# FordACPAUX.net
KiCad netlist of a schematic drawn in EAGLE
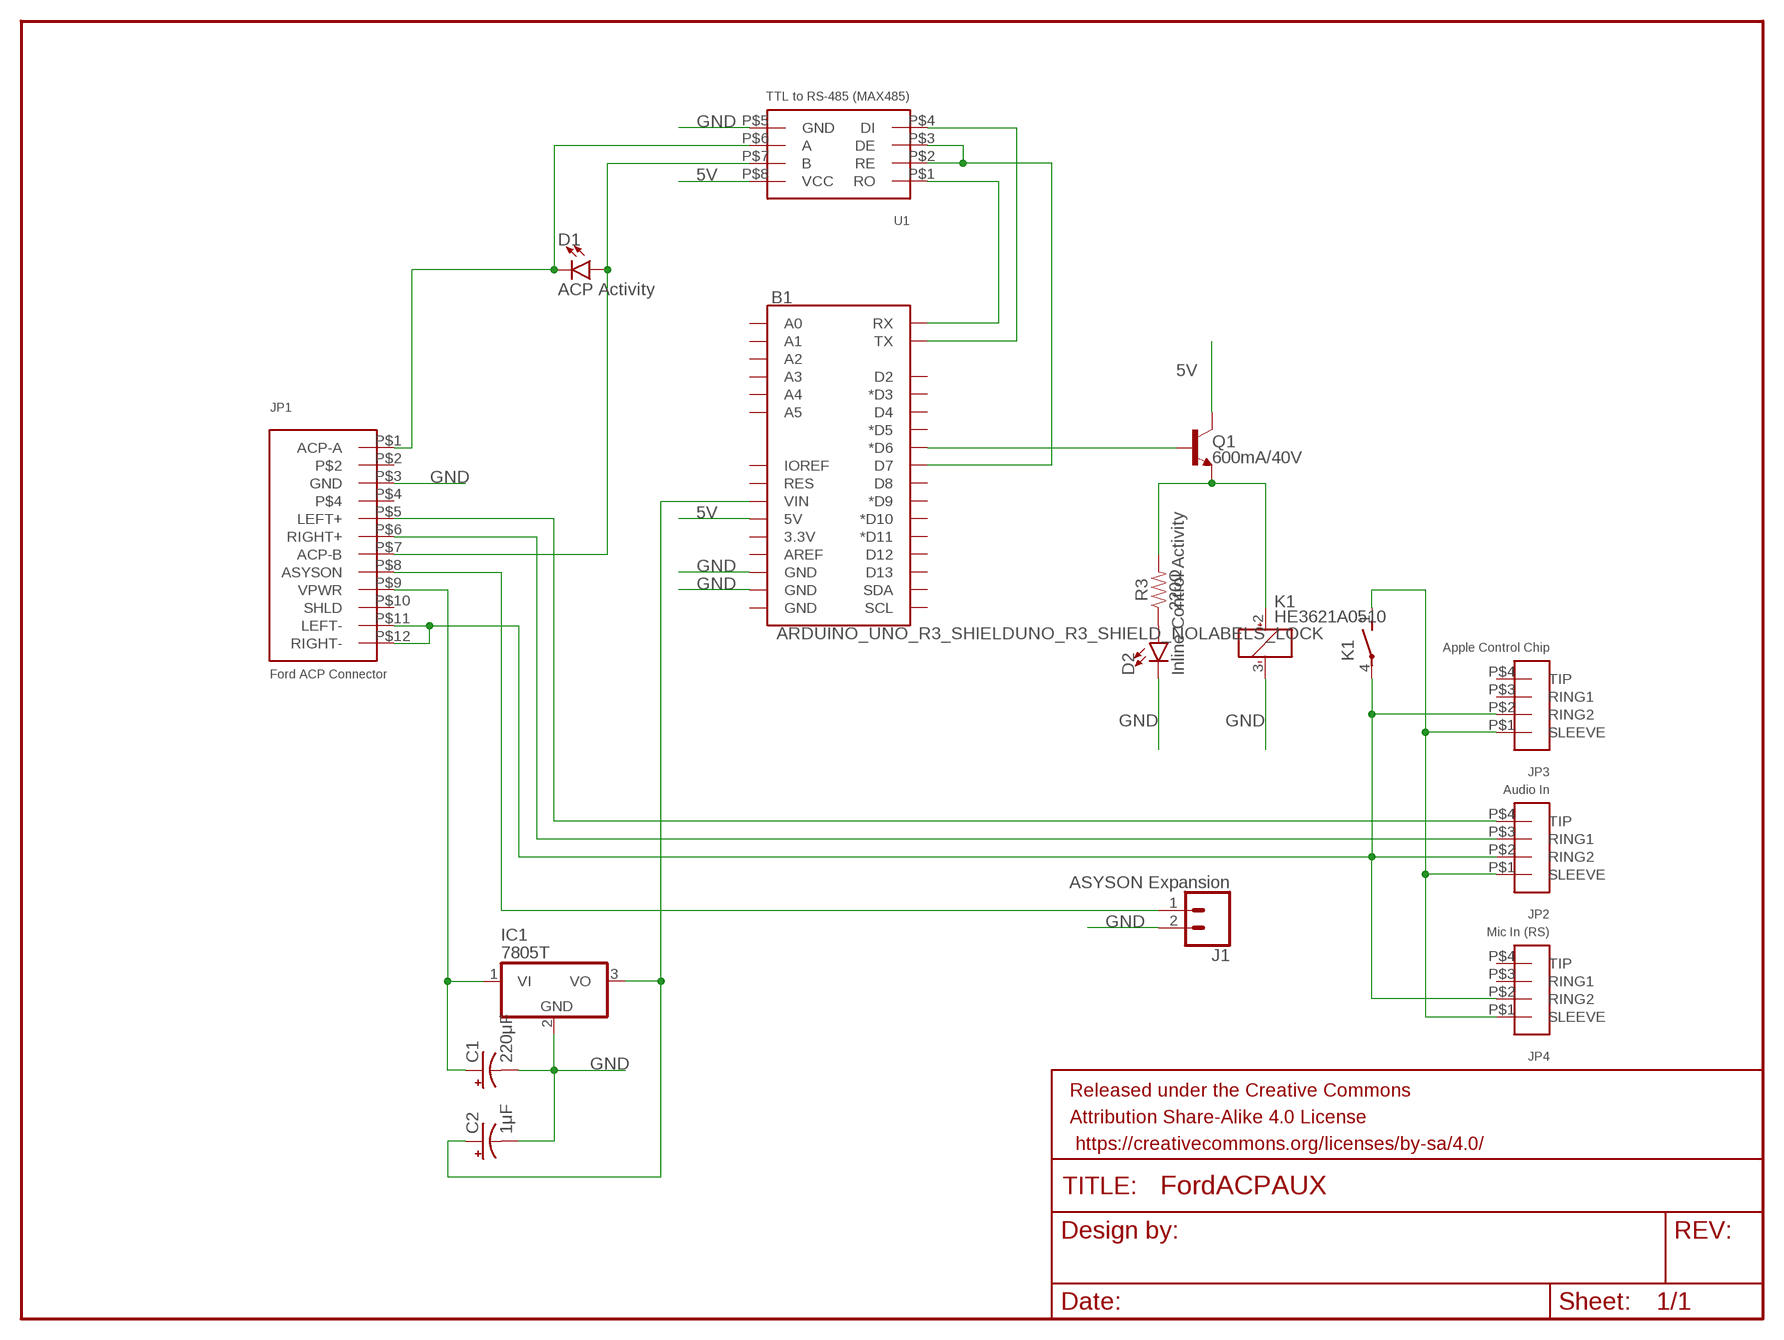
[diagram p0: schematic, sheet 1]

(export (version "E")
  (design (tool "Eeschema 10.0.6"))
  (components
    (comp (ref "B1")
      (value "ARDUINO_UNO_R3_SHIELDUNO_R3_SHIELD_NOLABELS_LOCK")
      (footprint "eagle-import:UNO_R3_SHIELD_NOLABELS_LOCK")
      (libsource (lib "eagle-import") (part "ARDUINO_UNO_R3_SHIELDUNO_R3_SHIELD_NOLABELS_LOCK"))
    )
    (comp (ref "C1")
      (value "220μF")
      (footprint "eagle-import:E2,5-7")
      (libsource (lib "eagle-import") (part "CPOL-USE2.5-7"))
    )
    (comp (ref "C2")
      (value "1μF")
      (footprint "eagle-import:E2-4")
      (libsource (lib "eagle-import") (part "CPOL-USE2-4"))
    )
    (comp (ref "D1")
      (value "ACP Activity")
      (footprint "eagle-import:LED_3MM")
      (libsource (lib "eagle-import") (part "LED3MM"))
    )
    (comp (ref "D2")
      (value "Inline Control Activity")
      (footprint "eagle-import:LED_3MM")
      (libsource (lib "eagle-import") (part "LED3MM"))
    )
    (comp (ref "FRAME1")
      (value "FRAME-LETTERNO_PACKAGE")
      (footprint "eagle-import:DUMMY")
      (fields (field (name "DESIGNER") "Nobody"))
      (libsource (lib "eagle-import") (part "FRAME-LETTERNO_PACKAGE"))
    )
    (comp (ref "IC1")
      (value "7805T")
      (footprint "eagle-import:TO220H")
      (libsource (lib "eagle-import") (part "78T05"))
    )
    (comp (ref "J1")
      (value "ASYSON Expansion")
      (footprint "eagle-import:1X02_LOCK")
      (libsource (lib "eagle-import") (part "CONN_02LOCK"))
    )
    (comp (ref "JP1")
      (value "Ford ACP Connector")
      (footprint "eagle-import:AMP_174051-2_040_MULTILOCK")
      (libsource (lib "eagle-import") (part "AMP-174051-2_040_MULTILOCK"))
    )
    (comp (ref "JP2")
      (value "Audio In")
      (footprint "eagle-import:3-5MM_4_POLE_TRRS_PCB_MOUNT")
      (libsource (lib "eagle-import") (part "TRRS_JACK4_PIN_PCB_MOUNT"))
    )
    (comp (ref "JP3")
      (value "Apple Control Chip")
      (footprint "eagle-import:3-5MM_4_POLE_TRRS_PCB_MOUNT")
      (libsource (lib "eagle-import") (part "TRRS_JACK4_PIN_PCB_MOUNT"))
    )
    (comp (ref "JP4")
      (value "Mic In (RS)")
      (footprint "eagle-import:3-5MM_4_POLE_TRRS_PCB_MOUNT")
      (libsource (lib "eagle-import") (part "TRRS_JACK4_PIN_PCB_MOUNT"))
    )
    (comp (ref "K1")
      (value "HE3621A0510")
      (footprint "eagle-import:HE3621")
      (fields (field (name "MF") "HAMLIN") (field (name "MPN") "HE3621A2410"))
      (libsource (lib "eagle-import") (part "HE3621"))
    )
    (comp (ref "Q1")
      (value "600mA/40V")
      (footprint "eagle-import:TO-92")
      (libsource (lib "eagle-import") (part "TRANS_NPN-P2N2222A"))
    )
    (comp (ref "R3")
      (value "220Ω")
      (footprint "eagle-import:AXIAL-0.3")
      (libsource (lib "eagle-import") (part "RESISTORAXIAL-0.3"))
    )
    (comp (ref "U1")
      (value "TTL to RS-485 (MAX485)")
      (footprint "eagle-import:MAX485_TTL_TO_RS_485_MODULE")
      (libsource (lib "eagle-import") (part "MAX485_TTL_TO_RS_485_MODULE"))
    )
  )
  (nets
    (net (code "1") (name "/5V") (class "Default")
      (node (ref "B1") (pin "5V") (pinfunction "5V_5V") (pintype "bidirectional"))
      (node (ref "Q1") (pin "1") (pinfunction "C_1") (pintype "passive"))
      (node (ref "U1") (pin "P$8") (pinfunction "VCC_P$8") (pintype "power_in"))
    )
    (net (code "2") (name "/GND") (class "Default")
      (node (ref "B1") (pin "GND@1") (pinfunction "GND_GND@1") (pintype "bidirectional"))
      (node (ref "B1") (pin "GND@2") (pinfunction "GND_GND@2") (pintype "bidirectional"))
      (node (ref "C1") (pin "-") (pinfunction "-_-") (pintype "passive"))
      (node (ref "C2") (pin "-") (pinfunction "-_-") (pintype "passive"))
      (node (ref "D2") (pin "K") (pinfunction "C_K") (pintype "passive"))
      (node (ref "IC1") (pin "2") (pinfunction "GND_2") (pintype "passive"))
      (node (ref "J1") (pin "2") (pinfunction "2_2") (pintype "passive"))
      (node (ref "JP1") (pin "P$3") (pinfunction "GND_P$3") (pintype "power_in"))
      (node (ref "K1") (pin "3") (pinfunction "-_3") (pintype "passive"))
      (node (ref "U1") (pin "P$5") (pinfunction "GND_P$5") (pintype "power_in"))
    )
    (net (code "3") (name "Net-(B1-*D6)") (class "Default")
      (node (ref "B1") (pin "D6") (pinfunction "*D6_D6") (pintype "bidirectional"))
      (node (ref "Q1") (pin "2") (pinfunction "B_2") (pintype "passive"))
    )
    (net (code "4") (name "Net-(D1-C)") (class "Default")
      (node (ref "D1") (pin "K") (pinfunction "C_K") (pintype "passive"))
      (node (ref "JP1") (pin "P$1") (pinfunction "ACP-A_P$1") (pintype "bidirectional"))
      (node (ref "U1") (pin "P$6") (pinfunction "A_P$6") (pintype "bidirectional"))
    )
    (net (code "5") (name "Net-(IC1-VI)") (class "Default")
      (node (ref "C1") (pin "+") (pinfunction "+_+") (pintype "passive"))
      (node (ref "IC1") (pin "1") (pinfunction "VI_1") (pintype "input"))
      (node (ref "JP1") (pin "P$9") (pinfunction "VPWR_P$9") (pintype "power_in"))
    )
    (net (code "6") (name "Net-(IC1-VO)") (class "Default")
      (node (ref "B1") (pin "VIN") (pinfunction "VIN_VIN") (pintype "bidirectional"))
      (node (ref "C2") (pin "+") (pinfunction "+_+") (pintype "passive"))
      (node (ref "IC1") (pin "3") (pinfunction "VO_3") (pintype "passive"))
    )
    (net (code "7") (name "Net-(JP1-ACP-B)") (class "Default")
      (node (ref "D1") (pin "A") (pinfunction "A_A") (pintype "passive"))
      (node (ref "JP1") (pin "P$7") (pinfunction "ACP-B_P$7") (pintype "bidirectional"))
      (node (ref "U1") (pin "P$7") (pinfunction "B_P$7") (pintype "bidirectional"))
    )
    (net (code "8") (name "Net-(JP1-ASYSON)") (class "Default")
      (node (ref "J1") (pin "1") (pinfunction "1_1") (pintype "passive"))
      (node (ref "JP1") (pin "P$8") (pinfunction "ASYSON_P$8") (pintype "input"))
    )
    (net (code "9") (name "Net-(JP1-LEFT+)") (class "Default")
      (node (ref "JP1") (pin "P$5") (pinfunction "LEFT+_P$5") (pintype "output"))
      (node (ref "JP2") (pin "P$4") (pinfunction "TIP_P$4") (pintype "bidirectional"))
    )
    (net (code "10") (name "Net-(JP1-LEFT-)") (class "Default")
      (node (ref "JP1") (pin "P$11") (pinfunction "LEFT-_P$11") (pintype "input"))
      (node (ref "JP1") (pin "P$12") (pinfunction "RIGHT-_P$12") (pintype "input"))
      (node (ref "JP2") (pin "P$2") (pinfunction "RING2_P$2") (pintype "bidirectional"))
      (node (ref "JP3") (pin "P$2") (pinfunction "RING2_P$2") (pintype "bidirectional"))
      (node (ref "JP4") (pin "P$2") (pinfunction "RING2_P$2") (pintype "bidirectional"))
      (node (ref "K1") (pin "4") (pinfunction "P_4") (pintype "passive"))
    )
    (net (code "11") (name "Net-(JP1-RIGHT+)") (class "Default")
      (node (ref "JP1") (pin "P$6") (pinfunction "RIGHT+_P$6") (pintype "output"))
      (node (ref "JP2") (pin "P$3") (pinfunction "RING1_P$3") (pintype "bidirectional"))
    )
    (net (code "12") (name "Net-(JP2-SLEEVE)") (class "Default")
      (node (ref "JP2") (pin "P$1") (pinfunction "SLEEVE_P$1") (pintype "bidirectional"))
      (node (ref "JP3") (pin "P$1") (pinfunction "SLEEVE_P$1") (pintype "bidirectional"))
      (node (ref "JP4") (pin "P$1") (pinfunction "SLEEVE_P$1") (pintype "bidirectional"))
      (node (ref "K1") (pin "1") (pinfunction "S_1") (pintype "passive"))
    )
    (net (code "13") (name "Net-(K1A-+)") (class "Default")
      (node (ref "K1") (pin "2") (pinfunction "+_2") (pintype "passive"))
      (node (ref "Q1") (pin "3") (pinfunction "E_3") (pintype "passive"))
      (node (ref "R3") (pin "P$2") (pinfunction "2_P$2") (pintype "passive"))
    )
    (net (code "14") (name "Net-(R3-1)") (class "Default")
      (node (ref "D2") (pin "A") (pinfunction "A_A") (pintype "passive"))
      (node (ref "R3") (pin "P$1") (pinfunction "1_P$1") (pintype "passive"))
    )
    (net (code "15") (name "Net-(U1-DE)") (class "Default")
      (node (ref "B1") (pin "D7") (pinfunction "D7_D7") (pintype "bidirectional"))
      (node (ref "U1") (pin "P$2") (pinfunction "RE_P$2") (pintype "bidirectional"))
      (node (ref "U1") (pin "P$3") (pinfunction "DE_P$3") (pintype "bidirectional"))
    )
    (net (code "16") (name "Net-(U1-DI)") (class "Default")
      (node (ref "B1") (pin "TX") (pinfunction "TX_TX") (pintype "bidirectional"))
      (node (ref "U1") (pin "P$4") (pinfunction "DI_P$4") (pintype "input"))
    )
    (net (code "17") (name "Net-(U1-RO)") (class "Default")
      (node (ref "B1") (pin "RX") (pinfunction "RX_RX") (pintype "bidirectional"))
      (node (ref "U1") (pin "P$1") (pinfunction "RO_P$1") (pintype "output"))
    )
    (net (code "18") (name "unconnected-(B1-*D3-PadD3)") (class "Default")
      (node (ref "B1") (pin "D3") (pinfunction "*D3_D3") (pintype "bidirectional"))
    )
    (net (code "19") (name "unconnected-(B1-*D5-PadD5)") (class "Default")
      (node (ref "B1") (pin "D5") (pinfunction "*D5_D5") (pintype "bidirectional"))
    )
    (net (code "20") (name "unconnected-(B1-*D9-PadD9)") (class "Default")
      (node (ref "B1") (pin "D9") (pinfunction "*D9_D9") (pintype "bidirectional"))
    )
    (net (code "21") (name "unconnected-(B1-*D10-PadD10)") (class "Default")
      (node (ref "B1") (pin "D10") (pinfunction "*D10_D10") (pintype "bidirectional"))
    )
    (net (code "22") (name "unconnected-(B1-*D11-PadD11)") (class "Default")
      (node (ref "B1") (pin "D11") (pinfunction "*D11_D11") (pintype "bidirectional"))
    )
    (net (code "23") (name "unconnected-(B1-GND-PadGND@0)") (class "Default")
      (node (ref "B1") (pin "GND@0") (pinfunction "GND_GND@0") (pintype "bidirectional"))
    )
    (net (code "24") (name "unconnected-(B1-Pad3.3V)") (class "Default")
      (node (ref "B1") (pin "3.3V") (pinfunction "3.3V_3.3V") (pintype "bidirectional"))
    )
    (net (code "25") (name "unconnected-(B1-PadA0)") (class "Default")
      (node (ref "B1") (pin "A0") (pinfunction "A0_A0") (pintype "bidirectional"))
    )
    (net (code "26") (name "unconnected-(B1-PadA1)") (class "Default")
      (node (ref "B1") (pin "A1") (pinfunction "A1_A1") (pintype "bidirectional"))
    )
    (net (code "27") (name "unconnected-(B1-PadA2)") (class "Default")
      (node (ref "B1") (pin "A2") (pinfunction "A2_A2") (pintype "bidirectional"))
    )
    (net (code "28") (name "unconnected-(B1-PadA3)") (class "Default")
      (node (ref "B1") (pin "A3") (pinfunction "A3_A3") (pintype "bidirectional"))
    )
    (net (code "29") (name "unconnected-(B1-PadA4)") (class "Default")
      (node (ref "B1") (pin "A4") (pinfunction "A4_A4") (pintype "bidirectional"))
    )
    (net (code "30") (name "unconnected-(B1-PadA5)") (class "Default")
      (node (ref "B1") (pin "A5") (pinfunction "A5_A5") (pintype "bidirectional"))
    )
    (net (code "31") (name "unconnected-(B1-PadAREF)") (class "Default")
      (node (ref "B1") (pin "AREF") (pinfunction "AREF_AREF") (pintype "bidirectional"))
    )
    (net (code "32") (name "unconnected-(B1-PadD2)") (class "Default")
      (node (ref "B1") (pin "D2") (pinfunction "D2_D2") (pintype "bidirectional"))
    )
    (net (code "33") (name "unconnected-(B1-PadD4)") (class "Default")
      (node (ref "B1") (pin "D4") (pinfunction "D4_D4") (pintype "bidirectional"))
    )
    (net (code "34") (name "unconnected-(B1-PadD8)") (class "Default")
      (node (ref "B1") (pin "D8") (pinfunction "D8_D8") (pintype "bidirectional"))
    )
    (net (code "35") (name "unconnected-(B1-PadD12)") (class "Default")
      (node (ref "B1") (pin "D12") (pinfunction "D12_D12") (pintype "bidirectional"))
    )
    (net (code "36") (name "unconnected-(B1-PadD13)") (class "Default")
      (node (ref "B1") (pin "D13") (pinfunction "D13_D13") (pintype "bidirectional"))
    )
    (net (code "37") (name "unconnected-(B1-PadIOREF)") (class "Default")
      (node (ref "B1") (pin "IOREF") (pinfunction "IOREF_IOREF") (pintype "bidirectional"))
    )
    (net (code "38") (name "unconnected-(B1-PadRES)") (class "Default")
      (node (ref "B1") (pin "RES") (pinfunction "RES_RES") (pintype "bidirectional"))
    )
    (net (code "39") (name "unconnected-(B1-PadSCL)") (class "Default")
      (node (ref "B1") (pin "SCL") (pinfunction "SCL_SCL") (pintype "bidirectional"))
    )
    (net (code "40") (name "unconnected-(B1-PadSDA)") (class "Default")
      (node (ref "B1") (pin "SDA") (pinfunction "SDA_SDA") (pintype "bidirectional"))
    )
    (net (code "41") (name "unconnected-(JP1-PadP$2)") (class "Default")
      (node (ref "JP1") (pin "P$2") (pinfunction "P$2_P$2") (pintype "no_connect"))
    )
    (net (code "42") (name "unconnected-(JP1-PadP$4)") (class "Default")
      (node (ref "JP1") (pin "P$4") (pinfunction "P$4_P$4") (pintype "no_connect"))
    )
    (net (code "43") (name "unconnected-(JP1-SHLD-PadP$10)") (class "Default")
      (node (ref "JP1") (pin "P$10") (pinfunction "SHLD_P$10") (pintype "passive"))
    )
    (net (code "44") (name "unconnected-(JP3-RING1-PadP$3)") (class "Default")
      (node (ref "JP3") (pin "P$3") (pinfunction "RING1_P$3") (pintype "bidirectional"))
    )
    (net (code "45") (name "unconnected-(JP3-TIP-PadP$4)") (class "Default")
      (node (ref "JP3") (pin "P$4") (pinfunction "TIP_P$4") (pintype "bidirectional"))
    )
    (net (code "46") (name "unconnected-(JP4-RING1-PadP$3)") (class "Default")
      (node (ref "JP4") (pin "P$3") (pinfunction "RING1_P$3") (pintype "bidirectional"))
    )
    (net (code "47") (name "unconnected-(JP4-TIP-PadP$4)") (class "Default")
      (node (ref "JP4") (pin "P$4") (pinfunction "TIP_P$4") (pintype "bidirectional"))
    )
  )
)
